# 09-Peripherials.net
KiCad netlist of a schematic drawn in Altium Designer
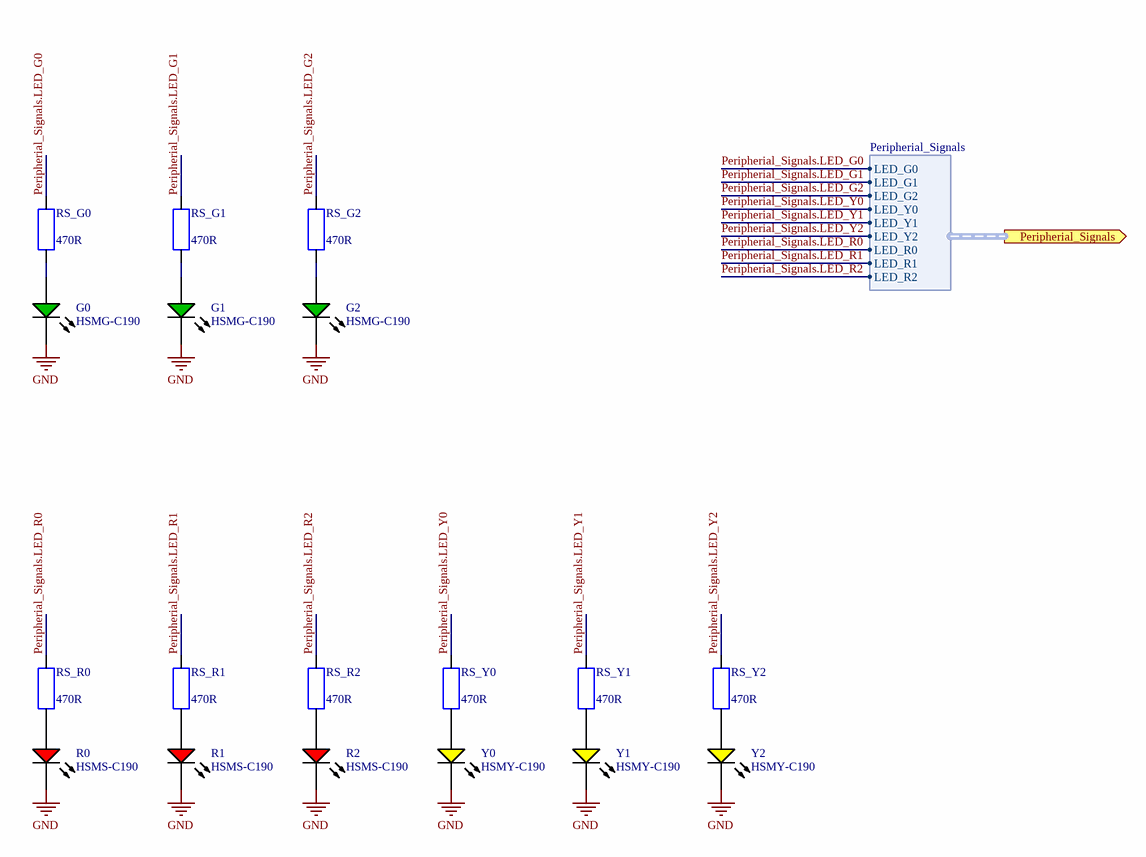
[diagram p0: 09-Peripherials.SchDoc]

(export (version "E")
  (design (tool "Eeschema 10.0.6"))
  (components
    (comp (ref "G0")
      (value "HSMG-C190")
      (footprint "AVAG-HSMX-C190_V")
      (description "Chip LED, Green, 2.2 V, -40 to 85 degC, 2-Pin SMD, RoHS, Tape and Reel")
      (libsource (lib "Altium Content Vault") (part "LED-GREEN-AK-2"))
    )
    (comp (ref "G1")
      (value "HSMG-C190")
      (footprint "AVAG-HSMX-C190_V")
      (description "Chip LED, Green, 2.2 V, -40 to 85 degC, 2-Pin SMD, RoHS, Tape and Reel")
      (libsource (lib "Altium Content Vault") (part "LED-GREEN-AK-2"))
    )
    (comp (ref "G2")
      (value "HSMG-C190")
      (footprint "AVAG-HSMX-C190_V")
      (description "Chip LED, Green, 2.2 V, -40 to 85 degC, 2-Pin SMD, RoHS, Tape and Reel")
      (libsource (lib "Altium Content Vault") (part "LED-GREEN-AK-2"))
    )
    (comp (ref "R0")
      (value "HSMS-C190")
      (footprint "AVAG-HSMX-C190_V")
      (description "LED Uni-Color Red, 52 mW, 20 mA, -40 to 85 degC, 2-Pin SMD, RoHS, Tape and Reel")
      (fields (field (name "MANUFACTURER") "Avago"))
      (libsource (lib "Altium Content Vault") (part "LED-RED-AK-2"))
    )
    (comp (ref "R1")
      (value "HSMS-C190")
      (footprint "AVAG-HSMX-C190_V")
      (description "LED Uni-Color Red, 52 mW, 20 mA, -40 to 85 degC, 2-Pin SMD, RoHS, Tape and Reel")
      (fields (field (name "MANUFACTURER") "Avago"))
      (libsource (lib "Altium Content Vault") (part "LED-RED-AK-2"))
    )
    (comp (ref "R2")
      (value "HSMS-C190")
      (footprint "AVAG-HSMX-C190_V")
      (description "LED Uni-Color Red, 52 mW, 20 mA, -40 to 85 degC, 2-Pin SMD, RoHS, Tape and Reel")
      (fields (field (name "MANUFACTURER") "Avago"))
      (libsource (lib "Altium Content Vault") (part "LED-RED-AK-2"))
    )
    (comp (ref "RS_G0")
      (value "RS")
      (footprint "0603_A")
      (fields
        (field (name "RESISTANCE") "470R")
        (field (name "POWER") "W100")
        (field (name "TOLERANCE") "1P00")
        (field (name "MANUFACTURER") "Yageo")
      )
      (libsource (lib "Bauteildb") (part "RS"))
    )
    (comp (ref "RS_G1")
      (value "RS")
      (footprint "0603_A")
      (fields
        (field (name "RESISTANCE") "470R")
        (field (name "POWER") "W100")
        (field (name "TOLERANCE") "1P00")
        (field (name "MANUFACTURER") "Yageo")
      )
      (libsource (lib "Bauteildb") (part "RS"))
    )
    (comp (ref "RS_G2")
      (value "RS")
      (footprint "0603_A")
      (fields
        (field (name "RESISTANCE") "470R")
        (field (name "POWER") "W100")
        (field (name "TOLERANCE") "1P00")
        (field (name "MANUFACTURER") "Yageo")
      )
      (libsource (lib "Bauteildb") (part "RS"))
    )
    (comp (ref "RS_R0")
      (value "RS")
      (footprint "0603_A")
      (fields
        (field (name "RESISTANCE") "470R")
        (field (name "POWER") "W100")
        (field (name "TOLERANCE") "1P00")
        (field (name "MANUFACTURER") "Yageo")
      )
      (libsource (lib "Bauteildb") (part "RS"))
    )
    (comp (ref "RS_R1")
      (value "RS")
      (footprint "0603_A")
      (fields
        (field (name "RESISTANCE") "470R")
        (field (name "POWER") "W100")
        (field (name "TOLERANCE") "1P00")
        (field (name "MANUFACTURER") "Yageo")
      )
      (libsource (lib "Bauteildb") (part "RS"))
    )
    (comp (ref "RS_R2")
      (value "RS")
      (footprint "0603_A")
      (fields
        (field (name "RESISTANCE") "470R")
        (field (name "POWER") "W100")
        (field (name "TOLERANCE") "1P00")
        (field (name "MANUFACTURER") "Yageo")
      )
      (libsource (lib "Bauteildb") (part "RS"))
    )
    (comp (ref "RS_Y0")
      (value "RS")
      (footprint "0603_A")
      (fields
        (field (name "RESISTANCE") "470R")
        (field (name "POWER") "W100")
        (field (name "TOLERANCE") "1P00")
        (field (name "MANUFACTURER") "Yageo")
      )
      (libsource (lib "Bauteildb") (part "RS"))
    )
    (comp (ref "RS_Y1")
      (value "RS")
      (footprint "0603_A")
      (fields
        (field (name "RESISTANCE") "470R")
        (field (name "POWER") "W100")
        (field (name "TOLERANCE") "1P00")
        (field (name "MANUFACTURER") "Yageo")
      )
      (libsource (lib "Bauteildb") (part "RS"))
    )
    (comp (ref "RS_Y2")
      (value "RS")
      (footprint "0603_A")
      (fields
        (field (name "RESISTANCE") "470R")
        (field (name "POWER") "W100")
        (field (name "TOLERANCE") "1P00")
        (field (name "MANUFACTURER") "Yageo")
      )
      (libsource (lib "Bauteildb") (part "RS"))
    )
    (comp (ref "Y0")
      (value "HSMY-C190")
      (footprint "AVAG-HSMX-C190_V")
      (description "LED Uni-Color Yellow, 65 mW, 20 mA, -40 to 85 degC, 2-Pin SMD, RoHS, Tape and Reel")
      (fields (field (name "TOLERANCE") "1%"))
      (libsource (lib "Altium Content Vault") (part "LED-YELLOW-AK-2"))
    )
    (comp (ref "Y1")
      (value "HSMY-C190")
      (footprint "AVAG-HSMX-C190_V")
      (description "LED Uni-Color Yellow, 65 mW, 20 mA, -40 to 85 degC, 2-Pin SMD, RoHS, Tape and Reel")
      (fields (field (name "TOLERANCE") "1%"))
      (libsource (lib "Altium Content Vault") (part "LED-YELLOW-AK-2"))
    )
    (comp (ref "Y2")
      (value "HSMY-C190")
      (footprint "AVAG-HSMX-C190_V")
      (description "LED Uni-Color Yellow, 65 mW, 20 mA, -40 to 85 degC, 2-Pin SMD, RoHS, Tape and Reel")
      (fields (field (name "TOLERANCE") "1%"))
      (libsource (lib "Altium Content Vault") (part "LED-YELLOW-AK-2"))
    )
  )
  (nets
    (net (code "2") (name "/Peripherial_Signals.LED_G0") (class "Default")
      (node (ref "RS_G0") (pin "2") (pintype "passive"))
    )
    (net (code "3") (name "/Peripherial_Signals.LED_G1") (class "Default")
      (node (ref "RS_G1") (pin "2") (pintype "passive"))
    )
    (net (code "4") (name "/Peripherial_Signals.LED_G2") (class "Default")
      (node (ref "RS_G2") (pin "2") (pintype "passive"))
    )
    (net (code "5") (name "/Peripherial_Signals.LED_R0") (class "Default")
      (node (ref "RS_R0") (pin "2") (pintype "passive"))
    )
    (net (code "6") (name "/Peripherial_Signals.LED_R1") (class "Default")
      (node (ref "RS_R1") (pin "2") (pintype "passive"))
    )
    (net (code "7") (name "/Peripherial_Signals.LED_R2") (class "Default")
      (node (ref "RS_R2") (pin "2") (pintype "passive"))
    )
    (net (code "8") (name "/Peripherial_Signals.LED_Y0") (class "Default")
      (node (ref "RS_Y0") (pin "2") (pintype "passive"))
    )
    (net (code "9") (name "/Peripherial_Signals.LED_Y1") (class "Default")
      (node (ref "RS_Y1") (pin "2") (pintype "passive"))
    )
    (net (code "10") (name "/Peripherial_Signals.LED_Y2") (class "Default")
      (node (ref "RS_Y2") (pin "2") (pintype "passive"))
    )
    (net (code "12") (name "GND") (class "Default")
      (node (ref "G0") (pin "2") (pinfunction "K_2") (pintype "passive"))
      (node (ref "G1") (pin "2") (pinfunction "K_2") (pintype "passive"))
      (node (ref "G2") (pin "2") (pinfunction "K_2") (pintype "passive"))
      (node (ref "R0") (pin "2") (pinfunction "K_2") (pintype "passive"))
      (node (ref "R1") (pin "2") (pinfunction "K_2") (pintype "passive"))
      (node (ref "R2") (pin "2") (pinfunction "K_2") (pintype "passive"))
      (node (ref "Y0") (pin "2") (pinfunction "K_2") (pintype "passive"))
      (node (ref "Y1") (pin "2") (pinfunction "K_2") (pintype "passive"))
      (node (ref "Y2") (pin "2") (pinfunction "K_2") (pintype "passive"))
    )
    (net (code "13") (name "Net-(G0-A)") (class "Default")
      (node (ref "G0") (pin "1") (pinfunction "A_1") (pintype "passive"))
      (node (ref "RS_G0") (pin "1") (pintype "passive"))
    )
    (net (code "14") (name "Net-(G1-A)") (class "Default")
      (node (ref "G1") (pin "1") (pinfunction "A_1") (pintype "passive"))
      (node (ref "RS_G1") (pin "1") (pintype "passive"))
    )
    (net (code "15") (name "Net-(G2-A)") (class "Default")
      (node (ref "G2") (pin "1") (pinfunction "A_1") (pintype "passive"))
      (node (ref "RS_G2") (pin "1") (pintype "passive"))
    )
    (net (code "16") (name "Net-(R0-A)") (class "Default")
      (node (ref "R0") (pin "1") (pinfunction "A_1") (pintype "passive"))
      (node (ref "RS_R0") (pin "1") (pintype "passive"))
    )
    (net (code "17") (name "Net-(R1-A)") (class "Default")
      (node (ref "R1") (pin "1") (pinfunction "A_1") (pintype "passive"))
      (node (ref "RS_R1") (pin "1") (pintype "passive"))
    )
    (net (code "18") (name "Net-(R2-A)") (class "Default")
      (node (ref "R2") (pin "1") (pinfunction "A_1") (pintype "passive"))
      (node (ref "RS_R2") (pin "1") (pintype "passive"))
    )
    (net (code "19") (name "Net-(Y0-A)") (class "Default")
      (node (ref "RS_Y0") (pin "1") (pintype "passive"))
      (node (ref "Y0") (pin "1") (pinfunction "A_1") (pintype "passive"))
    )
    (net (code "20") (name "Net-(Y1-A)") (class "Default")
      (node (ref "RS_Y1") (pin "1") (pintype "passive"))
      (node (ref "Y1") (pin "1") (pinfunction "A_1") (pintype "passive"))
    )
    (net (code "21") (name "Net-(Y2-A)") (class "Default")
      (node (ref "RS_Y2") (pin "1") (pintype "passive"))
      (node (ref "Y2") (pin "1") (pinfunction "A_1") (pintype "passive"))
    )
  )
)
